# ATmega328p_microcontroller.net
KiCad netlist of a schematic drawn in EAGLE
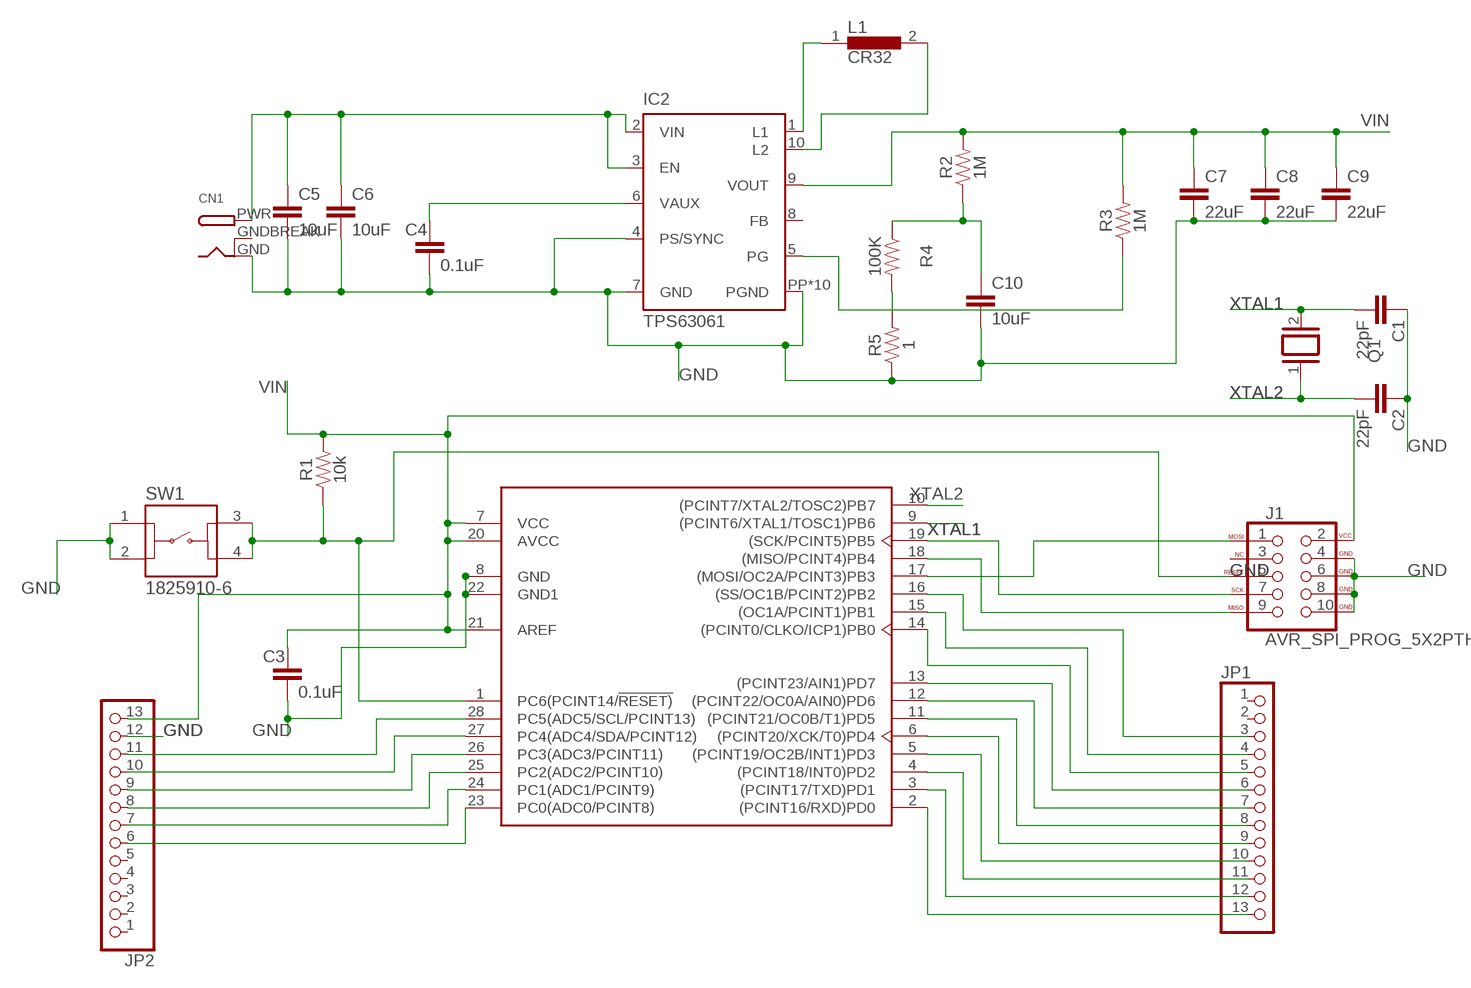
[diagram p0: schematic, sheet 1]

(export (version "E")
  (design (tool "Eeschema 10.0.6"))
  (components
    (comp (ref "C1")
      (value "22pF")
      (footprint "eagle-import:0603")
      (libsource (lib "eagle-import") (part "22PF-0603-50V-5%"))
    )
    (comp (ref "C2")
      (value "22pF")
      (footprint "eagle-import:0603")
      (libsource (lib "eagle-import") (part "22PF-0603-50V-5%"))
    )
    (comp (ref "C3")
      (value "0.1uF")
      (footprint "eagle-import:0402")
      (libsource (lib "eagle-import") (part "0.1UF-0402-16V-10%"))
    )
    (comp (ref "C4")
      (value "0.1uF")
      (footprint "eagle-import:0402")
      (libsource (lib "eagle-import") (part "0.1UF-0402-16V-10%"))
    )
    (comp (ref "C5")
      (value "10uF")
      (footprint "eagle-import:0603")
      (libsource (lib "eagle-import") (part "10UF-0603-6.3V-20%"))
    )
    (comp (ref "C6")
      (value "10uF")
      (footprint "eagle-import:0603")
      (libsource (lib "eagle-import") (part "10UF-0603-6.3V-20%"))
    )
    (comp (ref "C7")
      (value "22uF")
      (footprint "eagle-import:0805")
      (libsource (lib "eagle-import") (part "22UF-0805-6.3V-20%"))
    )
    (comp (ref "C8")
      (value "22uF")
      (footprint "eagle-import:0805")
      (libsource (lib "eagle-import") (part "22UF-0805-6.3V-20%"))
    )
    (comp (ref "C9")
      (value "22uF")
      (footprint "eagle-import:0805")
      (libsource (lib "eagle-import") (part "22UF-0805-6.3V-20%"))
    )
    (comp (ref "C10")
      (value "10uF")
      (footprint "eagle-import:0603")
      (libsource (lib "eagle-import") (part "10UF-0603-6.3V-20%"))
    )
    (comp (ref "CN1")
      (value "DCBARRELPTH")
      (footprint "eagle-import:DCJACK_2MM_PTH")
      (libsource (lib "eagle-import") (part "DCBARRELPTH"))
    )
    (comp (ref "IC2")
      (value "TPS63061")
      (footprint "eagle-import:DSC-S-PWSON-N10")
      (libsource (lib "eagle-import") (part "TPS63061"))
    )
    (comp (ref "J1")
      (value "AVR_SPI_PROG_5X2PTH")
      (footprint "eagle-import:2X5")
      (libsource (lib "eagle-import") (part "AVR_SPI_PROG_5X2PTH"))
    )
    (comp (ref "JP1")
      (value "PINHD-1X13")
      (footprint "eagle-import:1X13")
      (libsource (lib "eagle-import") (part "PINHD-1X13"))
    )
    (comp (ref "JP2")
      (value "PINHD-1X13")
      (footprint "eagle-import:1X13")
      (libsource (lib "eagle-import") (part "PINHD-1X13"))
    )
    (comp (ref "L1")
      (value "CR32")
      (footprint "eagle-import:CR32")
      (libsource (lib "eagle-import") (part "CR32"))
    )
    (comp (ref "Q1")
      (value "XTAL/S")
      (footprint "eagle-import:QS")
      (libsource (lib "eagle-import") (part "XTAL/S"))
    )
    (comp (ref "R1")
      (value "10k")
      (footprint "eagle-import:0603")
      (libsource (lib "eagle-import") (part "10KOHM-0603-1/10W-1%"))
    )
    (comp (ref "R2")
      (value "1M")
      (footprint "eagle-import:0603")
      (libsource (lib "eagle-import") (part "1MOHM-0603-1/4W-5%"))
    )
    (comp (ref "R3")
      (value "1M")
      (footprint "eagle-import:0603")
      (libsource (lib "eagle-import") (part "1MOHM-0603-1/4W-5%"))
    )
    (comp (ref "R4")
      (value "100K")
      (footprint "eagle-import:0402")
      (libsource (lib "eagle-import") (part "100KOHM-0402-1/16W-1%"))
    )
    (comp (ref "R5")
      (value "1")
      (footprint "eagle-import:0603")
      (libsource (lib "eagle-import") (part "1OHM-0603-1/10W-1%"))
    )
    (comp (ref "SW1")
      (value "1825910-6")
      (footprint "eagle-import:1825910-6")
      (fields
        (field (name "DIGIKEY_PART_NUMBER") "450-1650-ND")
        (field (name "MANUFACTURER") "TE Connectivity ALCOSWITCH Switches")
        (field (name "CREATED_BY") " PCBLayout.com")
      )
      (libsource (lib "eagle-import") (part "1825910-6"))
    )
    (comp (ref "U1")
      (value "ATMEGA328P-PU")
      (footprint "eagle-import:DIP-28")
      (fields
        (field (name "DIGIKEY_PART_NUMBER") "ATMEGA328P-PU-ND")
        (field (name "MANUFACTURER") "Microchip Technology")
        (field (name "CREATED_BY") "PCBLayout.com")
      )
      (libsource (lib "eagle-import") (part "ATMEGA328P-PU"))
    )
  )
  (nets
    (net (code "1") (name "/GND") (class "Default")
      (node (ref "C1") (pin "1") (pinfunction "1_1") (pintype "passive"))
      (node (ref "C10") (pin "2") (pinfunction "2_2") (pintype "passive"))
      (node (ref "C2") (pin "1") (pinfunction "1_1") (pintype "passive"))
      (node (ref "C3") (pin "2") (pinfunction "2_2") (pintype "passive"))
      (node (ref "C4") (pin "2") (pinfunction "2_2") (pintype "passive"))
      (node (ref "C5") (pin "2") (pinfunction "2_2") (pintype "passive"))
      (node (ref "C6") (pin "2") (pinfunction "2_2") (pintype "passive"))
      (node (ref "C7") (pin "2") (pinfunction "2_2") (pintype "passive"))
      (node (ref "C8") (pin "2") (pinfunction "2_2") (pintype "passive"))
      (node (ref "C9") (pin "2") (pinfunction "2_2") (pintype "passive"))
      (node (ref "CN1") (pin "GND") (pinfunction "GND_GND") (pintype "power_in"))
      (node (ref "IC2") (pin "4") (pinfunction "PS/SYNC_4") (pintype "input"))
      (node (ref "IC2") (pin "7") (pinfunction "GND_7") (pintype "input"))
      (node (ref "IC2") (pin "PP") (pinfunction "PGND_PP") (pintype "power_in"))
      (node (ref "IC2") (pin "PP@1") (pinfunction "PGND_PP@1") (pintype "power_in"))
      (node (ref "IC2") (pin "PP@10") (pinfunction "PGND_PP@10") (pintype "power_in"))
      (node (ref "IC2") (pin "PP@2") (pinfunction "PGND_PP@2") (pintype "power_in"))
      (node (ref "IC2") (pin "PP@3") (pinfunction "PGND_PP@3") (pintype "power_in"))
      (node (ref "IC2") (pin "PP@4") (pinfunction "PGND_PP@4") (pintype "power_in"))
      (node (ref "IC2") (pin "PP@5") (pinfunction "PGND_PP@5") (pintype "power_in"))
      (node (ref "IC2") (pin "PP@7") (pinfunction "PGND_PP@7") (pintype "power_in"))
      (node (ref "IC2") (pin "PP@8") (pinfunction "PGND_PP@8") (pintype "power_in"))
      (node (ref "IC2") (pin "PP@9") (pinfunction "PGND_PP@9") (pintype "power_in"))
      (node (ref "J1") (pin "10") (pinfunction "GND_10") (pintype "power_in"))
      (node (ref "J1") (pin "4") (pinfunction "GND_4") (pintype "power_in"))
      (node (ref "J1") (pin "6") (pinfunction "GND_6") (pintype "power_in"))
      (node (ref "J1") (pin "8") (pinfunction "GND_8") (pintype "power_in"))
      (node (ref "JP2") (pin "12") (pinfunction "12_12") (pintype "passive"))
      (node (ref "R5") (pin "1") (pinfunction "1_1") (pintype "passive"))
      (node (ref "SW1") (pin "1") (pinfunction "1_1") (pintype "passive"))
      (node (ref "SW1") (pin "2") (pinfunction "2_2") (pintype "passive"))
      (node (ref "U1") (pin "22") (pinfunction "GND1_22") (pintype "power_in"))
      (node (ref "U1") (pin "8") (pinfunction "GND_8") (pintype "power_in"))
    )
    (net (code "2") (name "/GNDBREAK") (class "Default")
      (node (ref "CN1") (pin "GNDBREAK") (pinfunction "GNDBREAK_GNDBREAK") (pintype "power_in"))
    )
    (net (code "3") (name "/VIN") (class "Default")
      (node (ref "C3") (pin "1") (pinfunction "1_1") (pintype "passive"))
      (node (ref "C7") (pin "1") (pinfunction "1_1") (pintype "passive"))
      (node (ref "C8") (pin "1") (pinfunction "1_1") (pintype "passive"))
      (node (ref "C9") (pin "1") (pinfunction "1_1") (pintype "passive"))
      (node (ref "IC2") (pin "9") (pinfunction "VOUT_9") (pintype "output"))
      (node (ref "J1") (pin "2") (pinfunction "VCC_2") (pintype "power_in"))
      (node (ref "JP2") (pin "13") (pinfunction "13_13") (pintype "passive"))
      (node (ref "R1") (pin "2") (pinfunction "2_2") (pintype "passive"))
      (node (ref "R2") (pin "2") (pinfunction "2_2") (pintype "passive"))
      (node (ref "R3") (pin "2") (pinfunction "2_2") (pintype "passive"))
      (node (ref "U1") (pin "20") (pinfunction "AVCC_20") (pintype "power_in"))
      (node (ref "U1") (pin "21") (pinfunction "AREF_21") (pintype "input"))
      (node (ref "U1") (pin "7") (pinfunction "VCC_7") (pintype "power_in"))
    )
    (net (code "4") (name "/XTAL1") (class "Default")
      (node (ref "C1") (pin "2") (pinfunction "2_2") (pintype "passive"))
      (node (ref "Q1") (pin "2") (pinfunction "2_2") (pintype "passive"))
      (node (ref "U1") (pin "9") (pinfunction "(PCINT6/XTAL1/TOSC1)PB6_9") (pintype "bidirectional"))
    )
    (net (code "5") (name "/XTAL2") (class "Default")
      (node (ref "C2") (pin "2") (pinfunction "2_2") (pintype "passive"))
      (node (ref "Q1") (pin "1") (pinfunction "1_1") (pintype "passive"))
      (node (ref "U1") (pin "10") (pinfunction "(PCINT7/XTAL2/TOSC2)PB7_10") (pintype "bidirectional"))
    )
    (net (code "6") (name "Net-(C10-Pad1)") (class "Default")
      (node (ref "C10") (pin "1") (pinfunction "1_1") (pintype "passive"))
      (node (ref "R2") (pin "1") (pinfunction "1_1") (pintype "passive"))
      (node (ref "R4") (pin "1") (pinfunction "1_1") (pintype "passive"))
    )
    (net (code "7") (name "Net-(IC2-EN)") (class "Default")
      (node (ref "C5") (pin "1") (pinfunction "1_1") (pintype "passive"))
      (node (ref "C6") (pin "1") (pinfunction "1_1") (pintype "passive"))
      (node (ref "CN1") (pin "PWR") (pinfunction "PWR_PWR") (pintype "power_in"))
      (node (ref "IC2") (pin "2") (pinfunction "VIN_2") (pintype "input"))
      (node (ref "IC2") (pin "3") (pinfunction "EN_3") (pintype "input"))
    )
    (net (code "8") (name "Net-(IC2-L1)") (class "Default")
      (node (ref "IC2") (pin "1") (pinfunction "L1_1") (pintype "input"))
      (node (ref "L1") (pin "1") (pinfunction "1_1") (pintype "passive"))
    )
    (net (code "9") (name "Net-(IC2-L2)") (class "Default")
      (node (ref "IC2") (pin "10") (pinfunction "L2_10") (pintype "input"))
      (node (ref "L1") (pin "2") (pinfunction "2_2") (pintype "passive"))
    )
    (net (code "10") (name "Net-(IC2-PG)") (class "Default")
      (node (ref "IC2") (pin "5") (pinfunction "PG_5") (pintype "output"))
      (node (ref "R3") (pin "1") (pinfunction "1_1") (pintype "passive"))
    )
    (net (code "11") (name "Net-(IC2-VAUX)") (class "Default")
      (node (ref "C4") (pin "1") (pinfunction "1_1") (pintype "passive"))
      (node (ref "IC2") (pin "6") (pinfunction "VAUX_6") (pintype "power_in"))
    )
    (net (code "12") (name "Net-(J1-MISO)") (class "Default")
      (node (ref "J1") (pin "9") (pinfunction "MISO_9") (pintype "passive"))
      (node (ref "U1") (pin "18") (pinfunction "(MISO/PCINT4)PB4_18") (pintype "bidirectional"))
    )
    (net (code "13") (name "Net-(J1-MOSI)") (class "Default")
      (node (ref "J1") (pin "1") (pinfunction "MOSI_1") (pintype "passive"))
      (node (ref "U1") (pin "17") (pinfunction "(MOSI/OC2A/PCINT3)PB3_17") (pintype "bidirectional"))
    )
    (net (code "14") (name "Net-(J1-RESET)") (class "Default")
      (node (ref "J1") (pin "5") (pinfunction "RESET_5") (pintype "passive"))
      (node (ref "R1") (pin "1") (pinfunction "1_1") (pintype "passive"))
      (node (ref "SW1") (pin "3") (pinfunction "3_3") (pintype "passive"))
      (node (ref "SW1") (pin "4") (pinfunction "4_4") (pintype "passive"))
      (node (ref "U1") (pin "1") (pinfunction "PC6(PCINT14/~{RESET})_1") (pintype "bidirectional"))
    )
    (net (code "15") (name "Net-(J1-SCK)") (class "Default")
      (node (ref "J1") (pin "7") (pinfunction "SCK_7") (pintype "passive"))
      (node (ref "U1") (pin "19") (pinfunction "(SCK/PCINT5)PB5_19") (pintype "bidirectional"))
    )
    (net (code "16") (name "Net-(R4-Pad2)") (class "Default")
      (node (ref "R4") (pin "2") (pinfunction "2_2") (pintype "passive"))
      (node (ref "R5") (pin "2") (pinfunction "2_2") (pintype "passive"))
    )
    (net (code "17") (name "Net-(U1-(OC1A{slash}PCINT1)PB1)") (class "Default")
      (node (ref "JP1") (pin "4") (pinfunction "4_4") (pintype "passive"))
      (node (ref "U1") (pin "15") (pinfunction "(OC1A/PCINT1)PB1_15") (pintype "bidirectional"))
    )
    (net (code "18") (name "Net-(U1-(PCINT0{slash}CLKO{slash}ICP1)PB0)") (class "Default")
      (node (ref "JP1") (pin "5") (pinfunction "5_5") (pintype "passive"))
      (node (ref "U1") (pin "14") (pinfunction "(PCINT0/CLKO/ICP1)PB0_14") (pintype "bidirectional"))
    )
    (net (code "19") (name "Net-(U1-(PCINT16{slash}RXD)PD0)") (class "Default")
      (node (ref "JP1") (pin "13") (pinfunction "13_13") (pintype "passive"))
      (node (ref "U1") (pin "2") (pinfunction "(PCINT16/RXD)PD0_2") (pintype "bidirectional"))
    )
    (net (code "20") (name "Net-(U1-(PCINT17{slash}TXD)PD1)") (class "Default")
      (node (ref "JP1") (pin "12") (pinfunction "12_12") (pintype "passive"))
      (node (ref "U1") (pin "3") (pinfunction "(PCINT17/TXD)PD1_3") (pintype "bidirectional"))
    )
    (net (code "21") (name "Net-(U1-(PCINT18{slash}INT0)PD2)") (class "Default")
      (node (ref "JP1") (pin "11") (pinfunction "11_11") (pintype "passive"))
      (node (ref "U1") (pin "4") (pinfunction "(PCINT18/INT0)PD2_4") (pintype "bidirectional"))
    )
    (net (code "22") (name "Net-(U1-(PCINT19{slash}OC2B{slash}INT1)PD3)") (class "Default")
      (node (ref "JP1") (pin "10") (pinfunction "10_10") (pintype "passive"))
      (node (ref "U1") (pin "5") (pinfunction "(PCINT19/OC2B/INT1)PD3_5") (pintype "bidirectional"))
    )
    (net (code "23") (name "Net-(U1-(PCINT20{slash}XCK{slash}T0)PD4)") (class "Default")
      (node (ref "JP1") (pin "9") (pinfunction "9_9") (pintype "passive"))
      (node (ref "U1") (pin "6") (pinfunction "(PCINT20/XCK/T0)PD4_6") (pintype "bidirectional"))
    )
    (net (code "24") (name "Net-(U1-(PCINT21{slash}OC0B{slash}T1)PD5)") (class "Default")
      (node (ref "JP1") (pin "8") (pinfunction "8_8") (pintype "passive"))
      (node (ref "U1") (pin "11") (pinfunction "(PCINT21/OC0B/T1)PD5_11") (pintype "bidirectional"))
    )
    (net (code "25") (name "Net-(U1-(PCINT22{slash}OC0A{slash}AIN0)PD6)") (class "Default")
      (node (ref "JP1") (pin "7") (pinfunction "7_7") (pintype "passive"))
      (node (ref "U1") (pin "12") (pinfunction "(PCINT22/OC0A/AIN0)PD6_12") (pintype "bidirectional"))
    )
    (net (code "26") (name "Net-(U1-(PCINT23{slash}AIN1)PD7)") (class "Default")
      (node (ref "JP1") (pin "6") (pinfunction "6_6") (pintype "passive"))
      (node (ref "U1") (pin "13") (pinfunction "(PCINT23/AIN1)PD7_13") (pintype "bidirectional"))
    )
    (net (code "27") (name "Net-(U1-(SS{slash}OC1B{slash}PCINT2)PB2)") (class "Default")
      (node (ref "JP1") (pin "3") (pinfunction "3_3") (pintype "passive"))
      (node (ref "U1") (pin "16") (pinfunction "(SS/OC1B/PCINT2)PB2_16") (pintype "bidirectional"))
    )
    (net (code "28") (name "Net-(U1-PC0(ADC0{slash}PCINT8))") (class "Default")
      (node (ref "JP2") (pin "6") (pinfunction "6_6") (pintype "passive"))
      (node (ref "U1") (pin "23") (pinfunction "PC0(ADC0/PCINT8)_23") (pintype "bidirectional"))
    )
    (net (code "29") (name "Net-(U1-PC1(ADC1{slash}PCINT9))") (class "Default")
      (node (ref "JP2") (pin "7") (pinfunction "7_7") (pintype "passive"))
      (node (ref "U1") (pin "24") (pinfunction "PC1(ADC1/PCINT9)_24") (pintype "bidirectional"))
    )
    (net (code "30") (name "Net-(U1-PC2(ADC2{slash}PCINT10))") (class "Default")
      (node (ref "JP2") (pin "8") (pinfunction "8_8") (pintype "passive"))
      (node (ref "U1") (pin "25") (pinfunction "PC2(ADC2/PCINT10)_25") (pintype "bidirectional"))
    )
    (net (code "31") (name "Net-(U1-PC3(ADC3{slash}PCINT11))") (class "Default")
      (node (ref "JP2") (pin "9") (pinfunction "9_9") (pintype "passive"))
      (node (ref "U1") (pin "26") (pinfunction "PC3(ADC3/PCINT11)_26") (pintype "bidirectional"))
    )
    (net (code "32") (name "Net-(U1-PC4(ADC4{slash}SDA{slash}PCINT12))") (class "Default")
      (node (ref "JP2") (pin "10") (pinfunction "10_10") (pintype "passive"))
      (node (ref "U1") (pin "27") (pinfunction "PC4(ADC4/SDA/PCINT12)_27") (pintype "bidirectional"))
    )
    (net (code "33") (name "Net-(U1-PC5(ADC5{slash}SCL{slash}PCINT13))") (class "Default")
      (node (ref "JP2") (pin "11") (pinfunction "11_11") (pintype "passive"))
      (node (ref "U1") (pin "28") (pinfunction "PC5(ADC5/SCL/PCINT13)_28") (pintype "bidirectional"))
    )
    (net (code "34") (name "unconnected-(IC2-FB-Pad8)") (class "Default")
      (node (ref "IC2") (pin "8") (pinfunction "FB_8") (pintype "input"))
    )
    (net (code "35") (name "unconnected-(J1-NC-Pad3)") (class "Default")
      (node (ref "J1") (pin "3") (pinfunction "NC_3") (pintype "no_connect"))
    )
    (net (code "36") (name "unconnected-(JP1-Pad1)") (class "Default")
      (node (ref "JP1") (pin "1") (pinfunction "1_1") (pintype "passive"))
    )
    (net (code "37") (name "unconnected-(JP1-Pad2)") (class "Default")
      (node (ref "JP1") (pin "2") (pinfunction "2_2") (pintype "passive"))
    )
    (net (code "38") (name "unconnected-(JP2-Pad1)") (class "Default")
      (node (ref "JP2") (pin "1") (pinfunction "1_1") (pintype "passive"))
    )
    (net (code "39") (name "unconnected-(JP2-Pad2)") (class "Default")
      (node (ref "JP2") (pin "2") (pinfunction "2_2") (pintype "passive"))
    )
    (net (code "40") (name "unconnected-(JP2-Pad3)") (class "Default")
      (node (ref "JP2") (pin "3") (pinfunction "3_3") (pintype "passive"))
    )
    (net (code "41") (name "unconnected-(JP2-Pad4)") (class "Default")
      (node (ref "JP2") (pin "4") (pinfunction "4_4") (pintype "passive"))
    )
    (net (code "42") (name "unconnected-(JP2-Pad5)") (class "Default")
      (node (ref "JP2") (pin "5") (pinfunction "5_5") (pintype "passive"))
    )
  )
)
